# A2235-H_brakeout.net
KiCad netlist of a schematic drawn in EAGLE
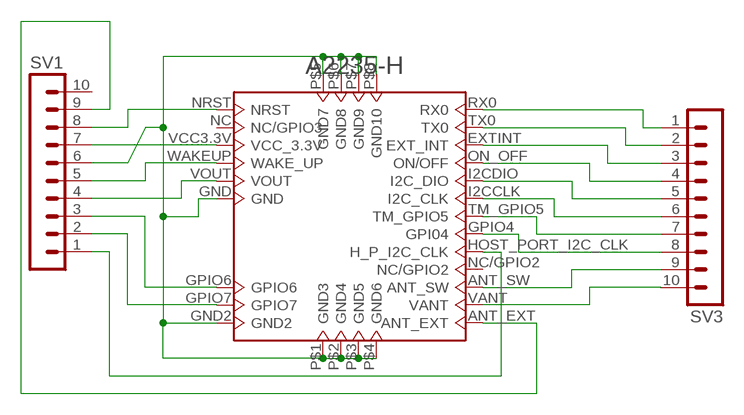
[diagram p0: schematic, sheet 1]

(export (version "E")
  (design (tool "Eeschema 10.0.6"))
  (components
    (comp (ref "SV1")
      (value "MA10-1")
      (footprint "eagle-import:MA10-1")
      (libsource (lib "eagle-import") (part "MA10-1"))
    )
    (comp (ref "SV3")
      (value "MA10-1")
      (footprint "eagle-import:MA10-1")
      (libsource (lib "eagle-import") (part "MA10-1"))
    )
    (comp (ref "U$1")
      (value "A2235-H")
      (footprint "eagle-import:A2235MAESTRO")
      (libsource (lib "eagle-import") (part "A2235-H"))
    )
  )
  (nets
    (net (code "1") (name "Net-(SV1-Pad2)") (class "Default")
      (node (ref "SV1") (pin "2") (pinfunction "2_2") (pintype "passive"))
      (node (ref "U$1") (pin "GPIO7") (pinfunction "GPIO7_GPIO7") (pintype "bidirectional"))
    )
    (net (code "2") (name "Net-(SV1-Pad3)") (class "Default")
      (node (ref "SV1") (pin "3") (pinfunction "3_3") (pintype "passive"))
      (node (ref "U$1") (pin "GPIO6") (pinfunction "GPIO6_GPIO6") (pintype "bidirectional"))
    )
    (net (code "3") (name "Net-(SV1-Pad4)") (class "Default")
      (node (ref "SV1") (pin "4") (pinfunction "4_4") (pintype "passive"))
      (node (ref "U$1") (pin "VOUT") (pinfunction "VOUT_VOUT") (pintype "bidirectional"))
    )
    (net (code "4") (name "Net-(SV1-Pad8)") (class "Default")
      (node (ref "SV1") (pin "8") (pinfunction "8_8") (pintype "passive"))
      (node (ref "U$1") (pin "NRST") (pinfunction "NRST_NRST") (pintype "bidirectional"))
    )
    (net (code "5") (name "Net-(SV1-Pad9)") (class "Default")
      (node (ref "SV1") (pin "9") (pinfunction "9_9") (pintype "passive"))
      (node (ref "U$1") (pin "ANT_EXT") (pinfunction "ANT_EXT_ANT_EXT") (pintype "bidirectional"))
    )
    (net (code "6") (name "Net-(SV3-Pad1)") (class "Default")
      (node (ref "SV3") (pin "1") (pinfunction "1_1") (pintype "passive"))
      (node (ref "U$1") (pin "RX0") (pinfunction "RX0_RX0") (pintype "bidirectional"))
    )
    (net (code "7") (name "Net-(SV3-Pad2)") (class "Default")
      (node (ref "SV3") (pin "2") (pinfunction "2_2") (pintype "passive"))
      (node (ref "U$1") (pin "TX0") (pinfunction "TX0_TX0") (pintype "bidirectional"))
    )
    (net (code "8") (name "Net-(SV3-Pad7)") (class "Default")
      (node (ref "SV3") (pin "7") (pinfunction "7_7") (pintype "passive"))
      (node (ref "U$1") (pin "TM_GPIO5") (pinfunction "TM_GPIO5_TM_GPIO5") (pintype "bidirectional"))
    )
    (net (code "9") (name "Net-(SV3-Pad9)") (class "Default")
      (node (ref "SV3") (pin "9") (pinfunction "9_9") (pintype "passive"))
      (node (ref "U$1") (pin "ANT_SW") (pinfunction "ANT_SW_ANT_SW") (pintype "bidirectional"))
    )
    (net (code "10") (name "Net-(SV3-Pad10)") (class "Default")
      (node (ref "SV3") (pin "10") (pinfunction "10_10") (pintype "passive"))
      (node (ref "U$1") (pin "VANT") (pinfunction "VANT_VANT") (pintype "bidirectional"))
    )
    (net (code "11") (name "Net-(U$1-EXT_INT)") (class "Default")
      (node (ref "SV3") (pin "3") (pinfunction "3_3") (pintype "passive"))
      (node (ref "U$1") (pin "EXTINT") (pinfunction "EXT_INT_EXTINT") (pintype "bidirectional"))
    )
    (net (code "12") (name "Net-(U$1-GND10)") (class "Default")
      (node (ref "SV1") (pin "6") (pinfunction "6_6") (pintype "passive"))
      (node (ref "U$1") (pin "GND") (pinfunction "GND_GND") (pintype "bidirectional"))
      (node (ref "U$1") (pin "GND2") (pinfunction "GND2_GND2") (pintype "bidirectional"))
      (node (ref "U$1") (pin "P$1") (pinfunction "GND3_P$1") (pintype "bidirectional"))
      (node (ref "U$1") (pin "P$2") (pinfunction "GND4_P$2") (pintype "bidirectional"))
      (node (ref "U$1") (pin "P$3") (pinfunction "GND5_P$3") (pintype "bidirectional"))
      (node (ref "U$1") (pin "P$4") (pinfunction "GND6_P$4") (pintype "bidirectional"))
      (node (ref "U$1") (pin "P$5") (pinfunction "GND7_P$5") (pintype "bidirectional"))
      (node (ref "U$1") (pin "P$6") (pinfunction "GND8_P$6") (pintype "bidirectional"))
      (node (ref "U$1") (pin "P$7") (pinfunction "GND9_P$7") (pintype "bidirectional"))
      (node (ref "U$1") (pin "P$8") (pinfunction "GND10_P$8") (pintype "bidirectional"))
    )
    (net (code "13") (name "Net-(U$1-GPI04)") (class "Default")
      (node (ref "SV3") (pin "8") (pinfunction "8_8") (pintype "passive"))
      (node (ref "U$1") (pin "GPIO4") (pinfunction "GPI04_GPIO4") (pintype "bidirectional"))
    )
    (net (code "14") (name "Net-(U$1-H_P_I2C_CLK)") (class "Default")
      (node (ref "SV1") (pin "1") (pinfunction "1_1") (pintype "passive"))
      (node (ref "U$1") (pin "HOST_PORT_I2C_CLK") (pinfunction "H_P_I2C_CLK_HOST_PORT_I2C_CLK") (pintype "bidirectional"))
    )
    (net (code "15") (name "Net-(U$1-I2C_CLK)") (class "Default")
      (node (ref "SV3") (pin "6") (pinfunction "6_6") (pintype "passive"))
      (node (ref "U$1") (pin "I2CCLK") (pinfunction "I2C_CLK_I2CCLK") (pintype "bidirectional"))
    )
    (net (code "16") (name "Net-(U$1-I2C_DIO)") (class "Default")
      (node (ref "SV3") (pin "5") (pinfunction "5_5") (pintype "passive"))
      (node (ref "U$1") (pin "I2CDIO") (pinfunction "I2C_DIO_I2CDIO") (pintype "bidirectional"))
    )
    (net (code "17") (name "Net-(U$1-ON{slash}OFF)") (class "Default")
      (node (ref "SV3") (pin "4") (pinfunction "4_4") (pintype "passive"))
      (node (ref "U$1") (pin "ON_OFF") (pinfunction "ON/OFF_ON_OFF") (pintype "bidirectional"))
    )
    (net (code "18") (name "Net-(U$1-VCC_3.3V)") (class "Default")
      (node (ref "SV1") (pin "7") (pinfunction "7_7") (pintype "passive"))
      (node (ref "U$1") (pin "VCC3.3V") (pinfunction "VCC_3.3V_VCC3.3V") (pintype "bidirectional"))
    )
    (net (code "19") (name "Net-(U$1-WAKE_UP)") (class "Default")
      (node (ref "SV1") (pin "5") (pinfunction "5_5") (pintype "passive"))
      (node (ref "U$1") (pin "WAKEUP") (pinfunction "WAKE_UP_WAKEUP") (pintype "bidirectional"))
    )
    (net (code "20") (name "unconnected-(SV1-Pad10)") (class "Default")
      (node (ref "SV1") (pin "10") (pinfunction "10_10") (pintype "passive"))
    )
    (net (code "21") (name "unconnected-(U$1-NC{slash}GPIO3-PadNC)") (class "Default")
      (node (ref "U$1") (pin "NC") (pinfunction "NC/GPIO3_NC") (pintype "bidirectional"))
    )
    (net (code "22") (name "unconnected-(U$1-PadNC{slash}GPIO2)") (class "Default")
      (node (ref "U$1") (pin "NC/GPIO2") (pinfunction "NC/GPIO2_NC/GPIO2") (pintype "bidirectional"))
    )
  )
)
